# RV1103.net
KiCad netlist of a schematic drawn in Altium Designer
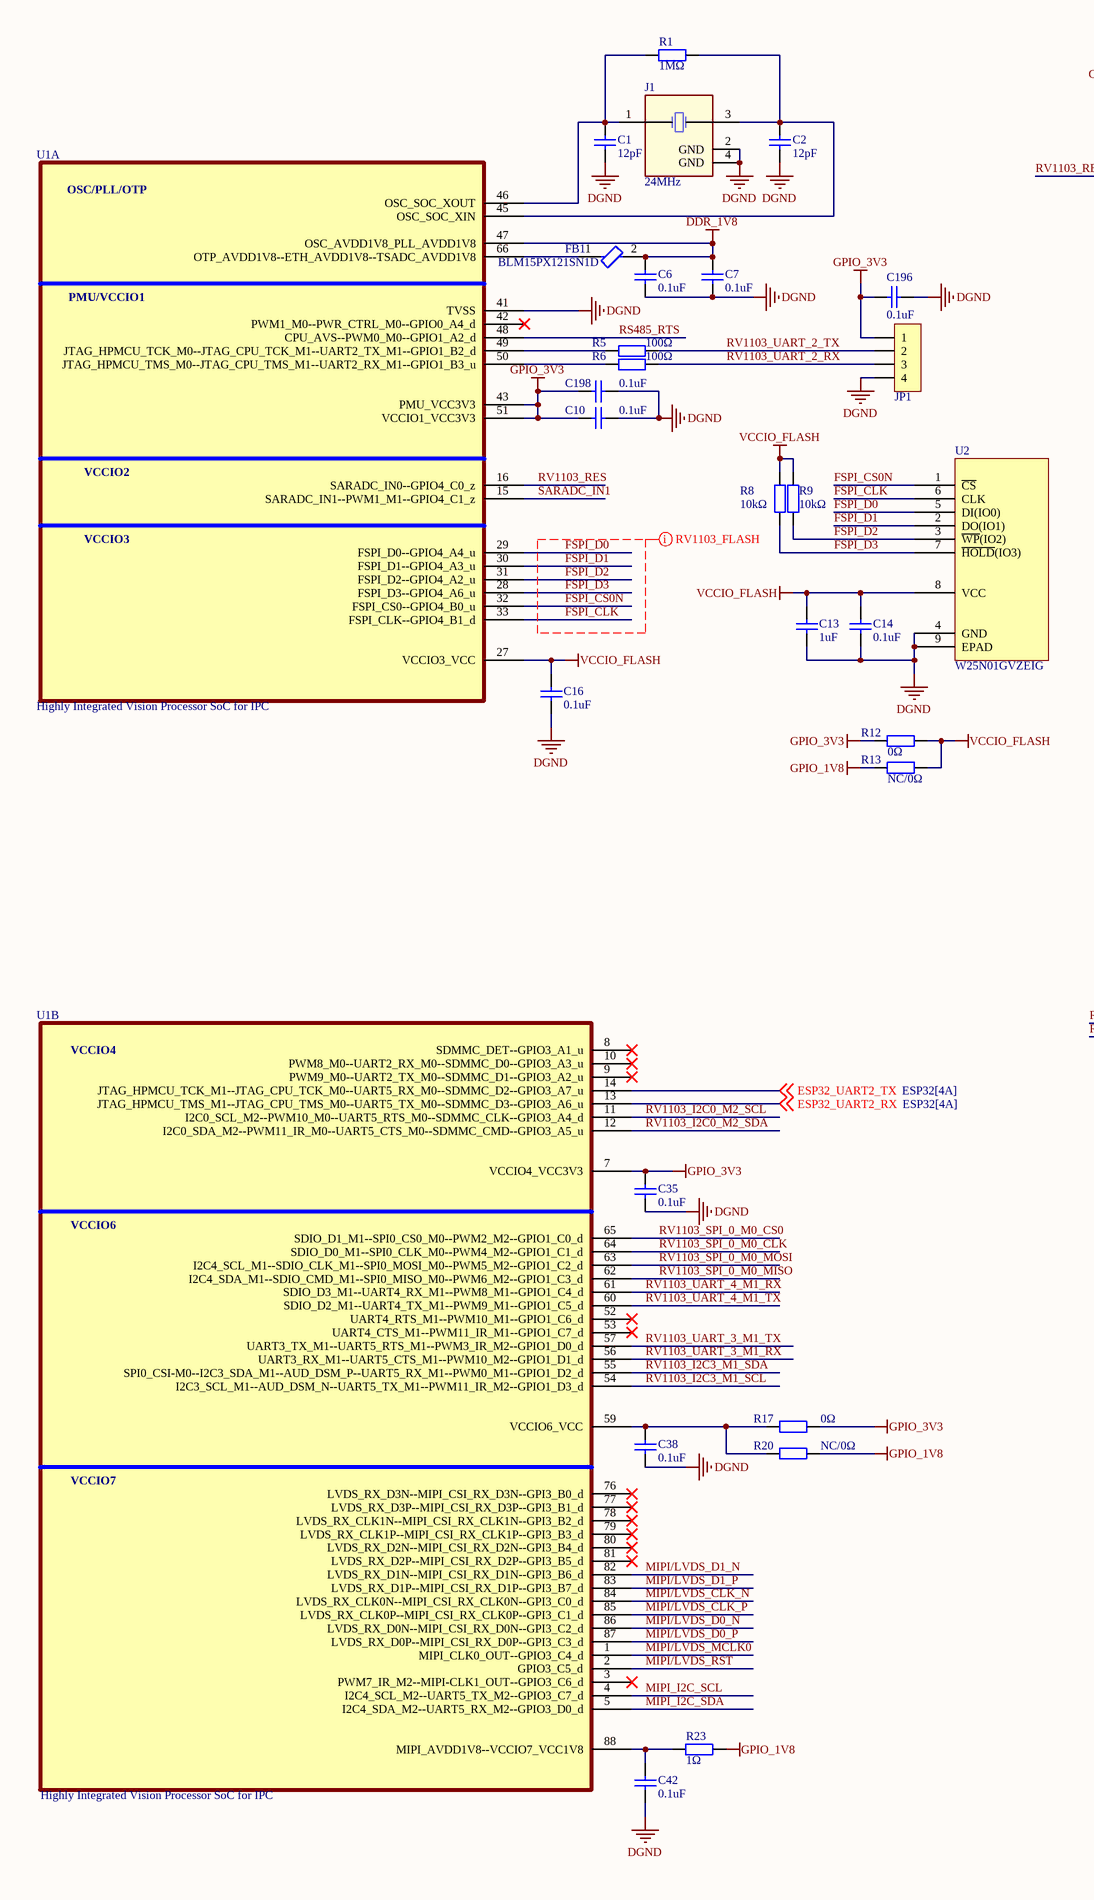
[diagram p0: RV1103.SchDoc, left]
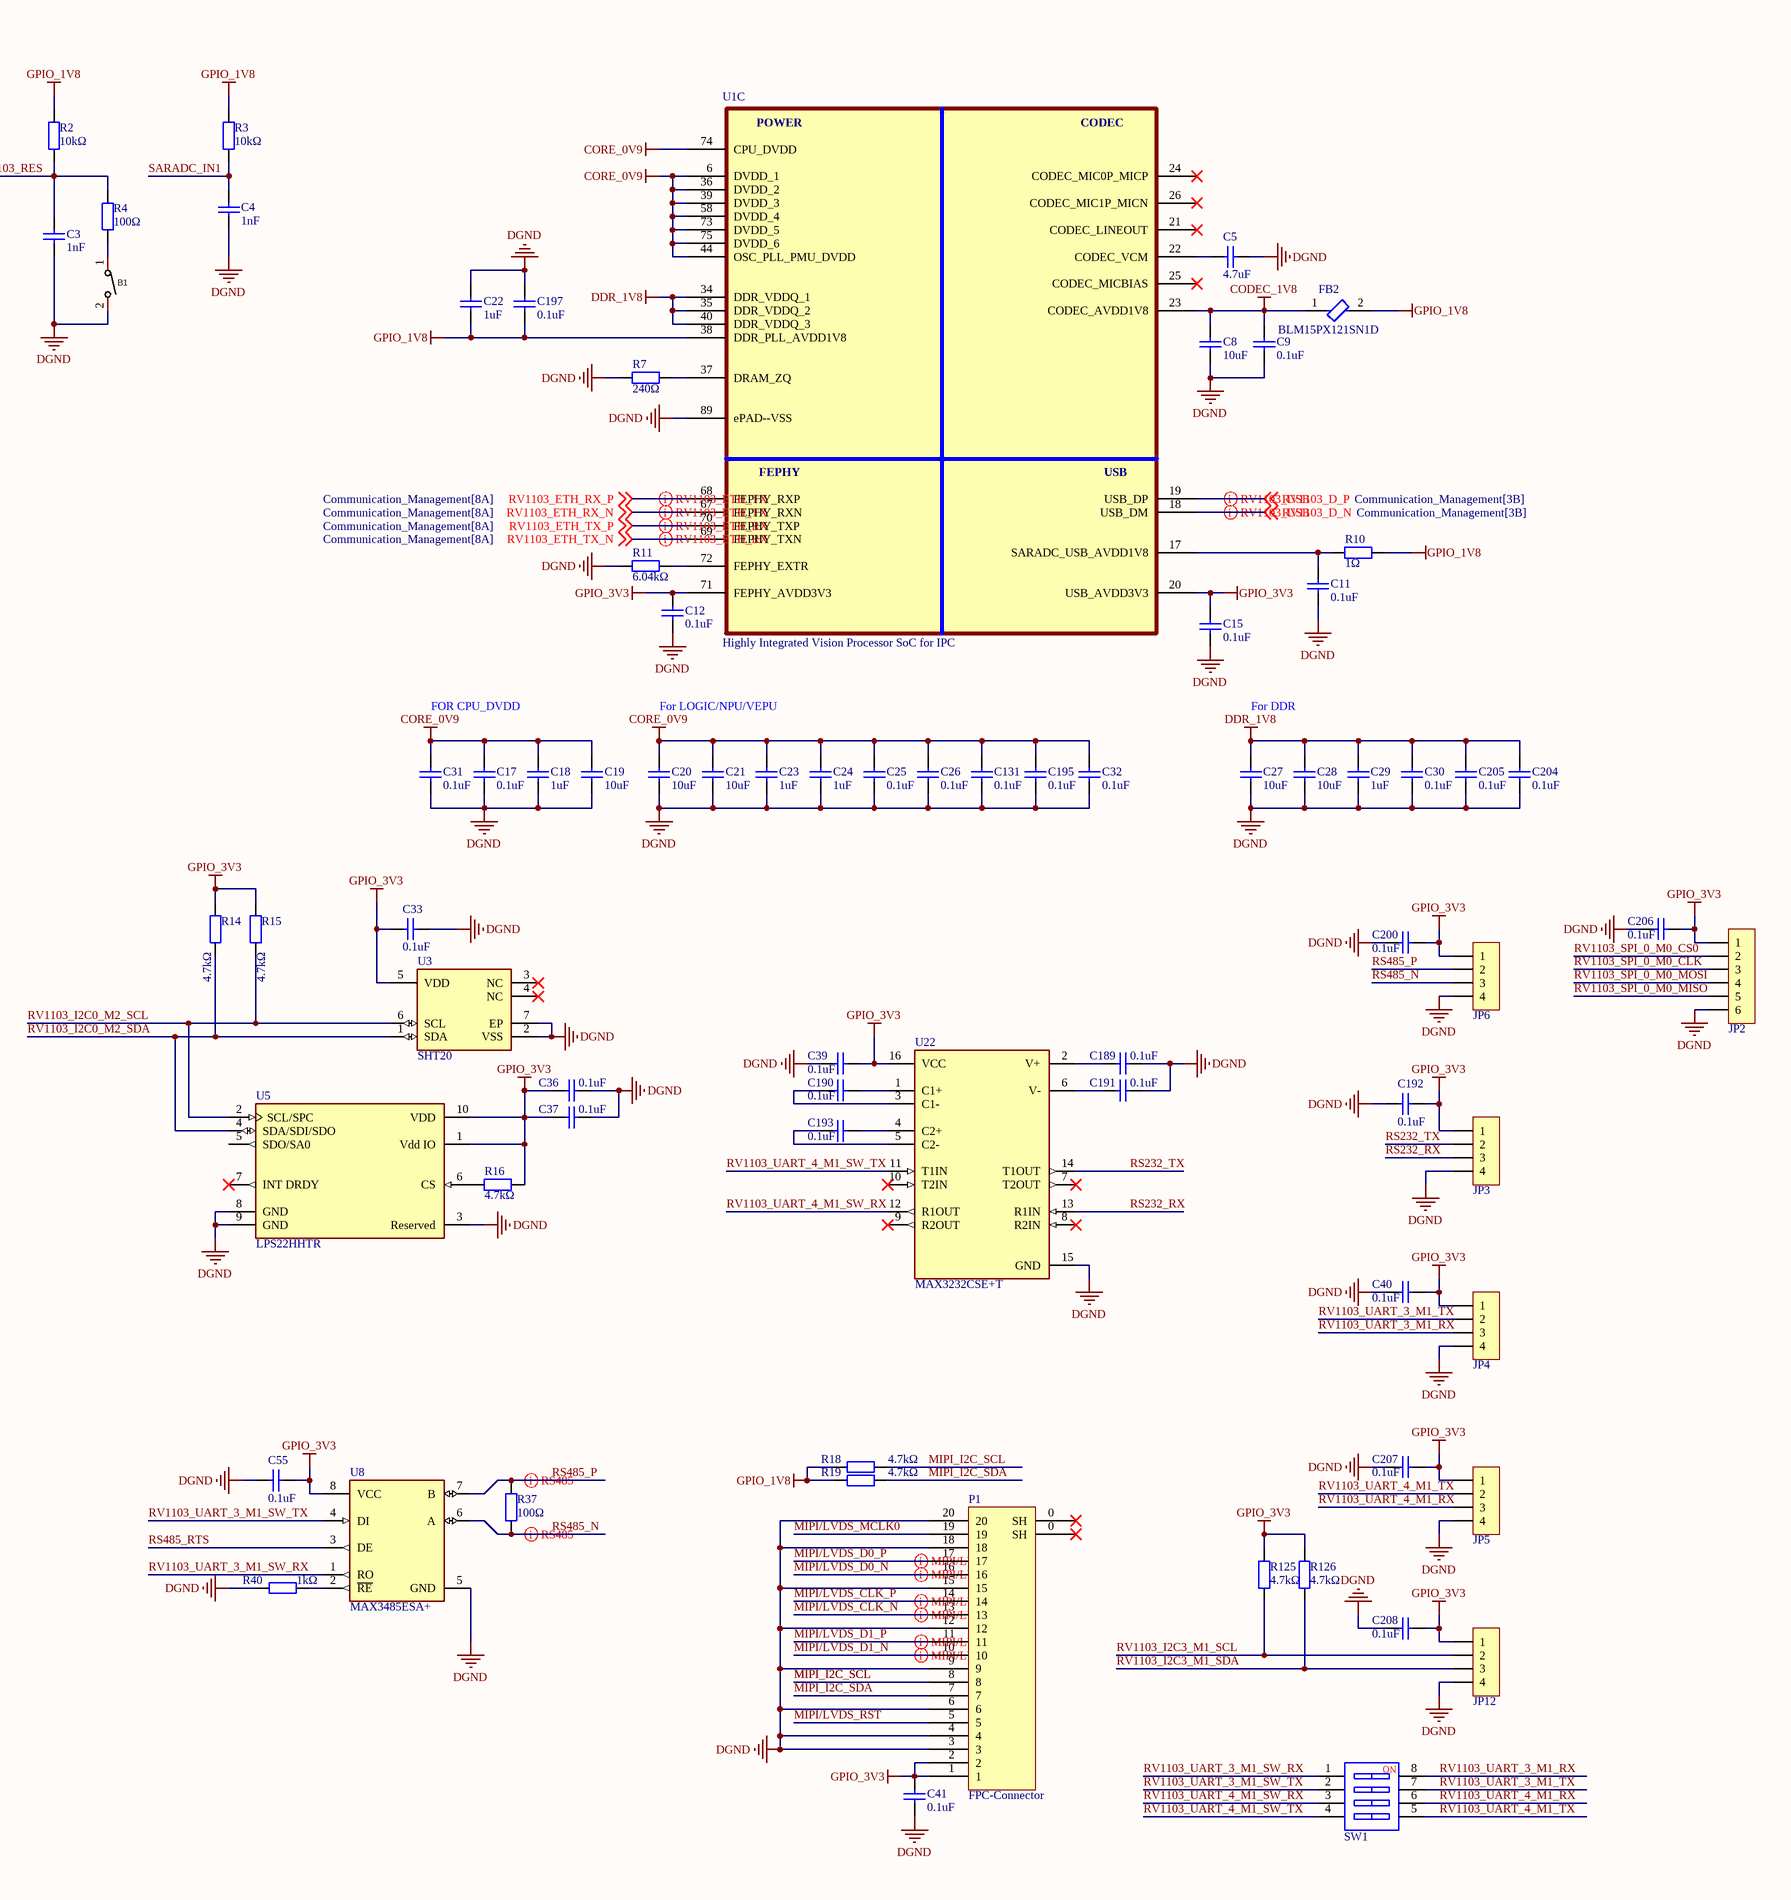
[diagram p1: RV1103.SchDoc, right]

(export (version "E")
  (design (tool "Eeschema 10.0.6"))
  (components
    (comp (ref "B1")
      (value "Bottom-2P-1Way")
      (footprint "SFerret:SW-SMD_L4.0-W2.9-LS5.0")
      (description "轻触按键")
      (fields (field (name "MANUFACTURER") "SHOU HAN(首韩)") (field (name "MANUFACTURER PART") "TS342A2P-WZ"))
      (libsource (lib "SFerret") (part "Bottom-2P-1Way"))
    )
    (comp (ref "C1")
      (value "12pF")
      (footprint "0402_C")
      (description "贴片电容")
      (libsource (lib "SFerret") (part "SMT_Cap"))
    )
    (comp (ref "C2")
      (value "12pF")
      (footprint "0402_C")
      (description "贴片电容")
      (libsource (lib "SFerret") (part "SMT_Cap"))
    )
    (comp (ref "C3")
      (value "1nF")
      (footprint "0402_C")
      (description "贴片电容")
      (libsource (lib "SFerret") (part "SMT_Cap"))
    )
    (comp (ref "C4")
      (value "1nF")
      (footprint "0402_C")
      (description "贴片电容")
      (libsource (lib "SFerret") (part "SMT_Cap"))
    )
    (comp (ref "C5")
      (value "4.7uF")
      (footprint "0402_C")
      (description "贴片电容")
      (libsource (lib "SFerret") (part "SMT_Cap"))
    )
    (comp (ref "C6")
      (value "0.1uF")
      (footprint "0402_C")
      (description "贴片电容")
      (libsource (lib "SFerret") (part "SMT_Cap"))
    )
    (comp (ref "C7")
      (value "0.1uF")
      (footprint "0402_C")
      (description "贴片电容")
      (libsource (lib "SFerret") (part "SMT_Cap"))
    )
    (comp (ref "C8")
      (value "10uF")
      (footprint "0402_C")
      (description "贴片电容")
      (libsource (lib "SFerret") (part "SMT_Cap"))
    )
    (comp (ref "C9")
      (value "0.1uF")
      (footprint "0402_C")
      (description "贴片电容")
      (libsource (lib "SFerret") (part "SMT_Cap"))
    )
    (comp (ref "C10")
      (value "0.1uF")
      (footprint "0402_C")
      (description "贴片电容")
      (libsource (lib "SFerret") (part "SMT_Cap"))
    )
    (comp (ref "C11")
      (value "0.1uF")
      (footprint "0402_C")
      (description "贴片电容")
      (libsource (lib "SFerret") (part "SMT_Cap"))
    )
    (comp (ref "C12")
      (value "0.1uF")
      (footprint "0402_C")
      (description "贴片电容")
      (libsource (lib "SFerret") (part "SMT_Cap"))
    )
    (comp (ref "C13")
      (value "1uF")
      (footprint "0603_C")
      (description "贴片电容")
      (libsource (lib "SFerret") (part "SMT_Cap"))
    )
    (comp (ref "C14")
      (value "0.1uF")
      (footprint "0603_C")
      (description "贴片电容")
      (libsource (lib "SFerret") (part "SMT_Cap"))
    )
    (comp (ref "C15")
      (value "0.1uF")
      (footprint "0402_C")
      (description "贴片电容")
      (libsource (lib "SFerret") (part "SMT_Cap"))
    )
    (comp (ref "C16")
      (value "0.1uF")
      (footprint "0402_C")
      (description "贴片电容")
      (libsource (lib "SFerret") (part "SMT_Cap"))
    )
    (comp (ref "C17")
      (value "0.1uF")
      (footprint "0402_C")
      (description "贴片电容")
      (libsource (lib "SFerret") (part "SMT_Cap"))
    )
    (comp (ref "C18")
      (value "1uF")
      (footprint "0402_C")
      (description "贴片电容")
      (libsource (lib "SFerret") (part "SMT_Cap"))
    )
    (comp (ref "C19")
      (value "10uF")
      (footprint "0603_C")
      (description "贴片电容")
      (libsource (lib "SFerret") (part "SMT_Cap"))
    )
    (comp (ref "C20")
      (value "10uF")
      (footprint "0603_C")
      (description "贴片电容")
      (libsource (lib "SFerret") (part "SMT_Cap"))
    )
    (comp (ref "C21")
      (value "10uF")
      (footprint "0603_C")
      (description "贴片电容")
      (libsource (lib "SFerret") (part "SMT_Cap"))
    )
    (comp (ref "C22")
      (value "1uF")
      (footprint "0402_C")
      (description "贴片电容")
      (libsource (lib "SFerret") (part "SMT_Cap"))
    )
    (comp (ref "C23")
      (value "1uF")
      (footprint "0402_C")
      (description "贴片电容")
      (libsource (lib "SFerret") (part "SMT_Cap"))
    )
    (comp (ref "C24")
      (value "1uF")
      (footprint "0402_C")
      (description "贴片电容")
      (libsource (lib "SFerret") (part "SMT_Cap"))
    )
    (comp (ref "C25")
      (value "0.1uF")
      (footprint "0402_C")
      (description "贴片电容")
      (libsource (lib "SFerret") (part "SMT_Cap"))
    )
    (comp (ref "C26")
      (value "0.1uF")
      (footprint "0402_C")
      (description "贴片电容")
      (libsource (lib "SFerret") (part "SMT_Cap"))
    )
    (comp (ref "C27")
      (value "10uF")
      (footprint "0603_C")
      (description "贴片电容")
      (libsource (lib "SFerret") (part "SMT_Cap"))
    )
    (comp (ref "C28")
      (value "10uF")
      (footprint "0603_C")
      (description "贴片电容")
      (libsource (lib "SFerret") (part "SMT_Cap"))
    )
    (comp (ref "C29")
      (value "1uF")
      (footprint "0402_C")
      (description "贴片电容")
      (libsource (lib "SFerret") (part "SMT_Cap"))
    )
    (comp (ref "C30")
      (value "0.1uF")
      (footprint "0402_C")
      (description "贴片电容")
      (libsource (lib "SFerret") (part "SMT_Cap"))
    )
    (comp (ref "C31")
      (value "0.1uF")
      (footprint "0402_C")
      (description "贴片电容")
      (libsource (lib "SFerret") (part "SMT_Cap"))
    )
    (comp (ref "C32")
      (value "0.1uF")
      (footprint "0402_C")
      (description "贴片电容")
      (libsource (lib "SFerret") (part "SMT_Cap"))
    )
    (comp (ref "C33")
      (value "0.1uF")
      (footprint "0603_C")
      (description "贴片电容")
      (libsource (lib "SFerret") (part "SMT_Cap"))
    )
    (comp (ref "C35")
      (value "0.1uF")
      (footprint "0402_C")
      (description "贴片电容")
      (libsource (lib "SFerret") (part "SMT_Cap"))
    )
    (comp (ref "C36")
      (value "0.1uF")
      (footprint "0603_C")
      (description "贴片电容")
      (libsource (lib "SFerret") (part "SMT_Cap"))
    )
    (comp (ref "C37")
      (value "0.1uF")
      (footprint "0603_C")
      (description "贴片电容")
      (libsource (lib "SFerret") (part "SMT_Cap"))
    )
    (comp (ref "C38")
      (value "0.1uF")
      (footprint "0402_C")
      (description "贴片电容")
      (libsource (lib "SFerret") (part "SMT_Cap"))
    )
    (comp (ref "C39")
      (value "0.1uF")
      (footprint "0603_C")
      (description "贴片电容")
      (libsource (lib "SFerret") (part "SMT_Cap"))
    )
    (comp (ref "C40")
      (value "0.1uF")
      (footprint "0603_C")
      (description "贴片电容")
      (libsource (lib "SFerret") (part "SMT_Cap"))
    )
    (comp (ref "C41")
      (value "0.1uF")
      (footprint "0603_C")
      (description "贴片电容")
      (libsource (lib "SFerret") (part "SMT_Cap"))
    )
    (comp (ref "C42")
      (value "0.1uF")
      (footprint "0402_C")
      (description "贴片电容")
      (libsource (lib "SFerret") (part "SMT_Cap"))
    )
    (comp (ref "C55")
      (value "0.1uF")
      (footprint "0603_C")
      (description "贴片电容")
      (libsource (lib "SFerret") (part "SMT_Cap"))
    )
    (comp (ref "C131")
      (value "0.1uF")
      (footprint "0402_C")
      (description "贴片电容")
      (libsource (lib "SFerret") (part "SMT_Cap"))
    )
    (comp (ref "C189")
      (value "0.1uF")
      (footprint "0603_C")
      (description "贴片电容")
      (libsource (lib "SFerret") (part "SMT_Cap"))
    )
    (comp (ref "C190")
      (value "0.1uF")
      (footprint "0603_C")
      (description "贴片电容")
      (libsource (lib "SFerret") (part "SMT_Cap"))
    )
    (comp (ref "C191")
      (value "0.1uF")
      (footprint "0603_C")
      (description "贴片电容")
      (libsource (lib "SFerret") (part "SMT_Cap"))
    )
    (comp (ref "C192")
      (value "0.1uF")
      (footprint "0603_C")
      (description "贴片电容")
      (libsource (lib "SFerret") (part "SMT_Cap"))
    )
    (comp (ref "C193")
      (value "0.1uF")
      (footprint "0603_C")
      (description "贴片电容")
      (libsource (lib "SFerret") (part "SMT_Cap"))
    )
    (comp (ref "C195")
      (value "0.1uF")
      (footprint "0402_C")
      (description "贴片电容")
      (libsource (lib "SFerret") (part "SMT_Cap"))
    )
    (comp (ref "C196")
      (value "0.1uF")
      (footprint "0603_C")
      (description "贴片电容")
      (libsource (lib "SFerret") (part "SMT_Cap"))
    )
    (comp (ref "C197")
      (value "0.1uF")
      (footprint "0402_C")
      (description "贴片电容")
      (libsource (lib "SFerret") (part "SMT_Cap"))
    )
    (comp (ref "C198")
      (value "0.1uF")
      (footprint "0402_C")
      (description "贴片电容")
      (libsource (lib "SFerret") (part "SMT_Cap"))
    )
    (comp (ref "C200")
      (value "0.1uF")
      (footprint "0603_C")
      (description "贴片电容")
      (libsource (lib "SFerret") (part "SMT_Cap"))
    )
    (comp (ref "C204")
      (value "0.1uF")
      (footprint "0402_C")
      (description "贴片电容")
      (libsource (lib "SFerret") (part "SMT_Cap"))
    )
    (comp (ref "C205")
      (value "0.1uF")
      (footprint "0402_C")
      (description "贴片电容")
      (libsource (lib "SFerret") (part "SMT_Cap"))
    )
    (comp (ref "C206")
      (value "0.1uF")
      (footprint "0603_C")
      (description "贴片电容")
      (libsource (lib "SFerret") (part "SMT_Cap"))
    )
    (comp (ref "C207")
      (value "0.1uF")
      (footprint "0603_C")
      (description "贴片电容")
      (libsource (lib "SFerret") (part "SMT_Cap"))
    )
    (comp (ref "C208")
      (value "0.1uF")
      (footprint "0603_C")
      (description "贴片电容")
      (libsource (lib "SFerret") (part "SMT_Cap"))
    )
    (comp (ref "FB1")
      (value "BLM15PX121SN1D")
      (footprint "FP-BLM15-0_05-d0_7-MFG")
      (description "Chip Ferrite Bead, 0402, 120Ω @ 100MHz, 0.055Ω, 25%, 2A")
      (fields (field (name "TOLERANCE") "25%"))
      (libsource (lib "Altium Content Vault") (part "5f30dd21d616792df468990f7003faa"))
    )
    (comp (ref "FB2")
      (value "BLM15PX121SN1D")
      (footprint "FP-BLM15-0_05-d0_7-MFG")
      (description "Chip Ferrite Bead, 0402, 120Ω @ 100MHz, 0.055Ω, 25%, 2A")
      (fields (field (name "TOLERANCE") "25%"))
      (libsource (lib "Altium Content Vault") (part "5f30dd21d616792df468990f7003faa"))
    )
    (comp (ref "J1")
      (value "24MHz")
      (footprint "SMD-2520_4P")
      (libsource (lib "SFerret") (part "Oscillator_SMT_4P"))
    )
    (comp (ref "JP1")
      (value "HDR-1X4")
      (footprint "MX 1.25-LS-4P")
      (description "4P接插件")
      (libsource (lib "5.0 - 接插件-脚距1.25") (part "Header 4"))
    )
    (comp (ref "JP2")
      (value "HDR-1X6")
      (footprint "MX 1.25-LS-6P")
      (description "6P接插件")
      (libsource (lib "5.0 - 接插件-脚距1.25") (part "Header 6"))
    )
    (comp (ref "JP3")
      (value "HDR-1X4")
      (footprint "MX 1.25-LS-4P")
      (description "4P接插件")
      (libsource (lib "5.0 - 接插件-脚距1.25") (part "Header 4"))
    )
    (comp (ref "JP4")
      (value "HDR-1X4")
      (footprint "MX 1.25-LS-4P")
      (description "4P接插件")
      (libsource (lib "5.0 - 接插件-脚距1.25") (part "Header 4"))
    )
    (comp (ref "JP5")
      (value "HDR-1X4")
      (footprint "MX 1.25-LS-4P")
      (description "4P接插件")
      (libsource (lib "5.0 - 接插件-脚距1.25") (part "Header 4"))
    )
    (comp (ref "JP6")
      (value "HDR-1X4")
      (footprint "MX 1.25-LS-4P")
      (description "4P接插件")
      (libsource (lib "5.0 - 接插件-脚距1.25") (part "Header 4"))
    )
    (comp (ref "JP12")
      (value "HDR-1X4")
      (footprint "MX 1.25-LS-4P")
      (description "4P接插件")
      (libsource (lib "5.0 - 接插件-脚距1.25") (part "Header 4"))
    )
    (comp (ref "P1")
      (value "FPC-Connector")
      (footprint "FPC0.5 2H-WS-20P")
      (libsource (lib "SFerret") (part "FFC/FPC-0.5-WS-20"))
    )
    (comp (ref "R1")
      (value "1MΩ")
      (footprint "0402_R")
      (description "贴片电阻")
      (libsource (lib "") (part "SMT_Res_1"))
    )
    (comp (ref "R2")
      (value "10kΩ")
      (footprint "0402_R")
      (description "贴片电阻")
      (libsource (lib "SFerret") (part "SMT_Res"))
    )
    (comp (ref "R3")
      (value "10kΩ")
      (footprint "0402_R")
      (description "贴片电阻")
      (libsource (lib "SFerret") (part "SMT_Res"))
    )
    (comp (ref "R4")
      (value "100Ω")
      (footprint "0402_R")
      (description "贴片电阻")
      (libsource (lib "SFerret") (part "SMT_Res"))
    )
    (comp (ref "R5")
      (value "100Ω")
      (footprint "0402_R")
      (description "贴片电阻")
      (libsource (lib "") (part "SMT_Res_1"))
    )
    (comp (ref "R6")
      (value "100Ω")
      (footprint "0402_R")
      (description "贴片电阻")
      (libsource (lib "") (part "SMT_Res_1"))
    )
    (comp (ref "R7")
      (value "240Ω")
      (footprint "0402_R")
      (description "贴片电阻")
      (libsource (lib "") (part "SMT_Res_1"))
    )
    (comp (ref "R8")
      (value "10kΩ")
      (footprint "0603_R")
      (description "贴片电阻")
      (libsource (lib "SFerret") (part "SMT_Res"))
    )
    (comp (ref "R9")
      (value "10kΩ")
      (footprint "0603_R")
      (description "贴片电阻")
      (libsource (lib "SFerret") (part "SMT_Res"))
    )
    (comp (ref "R10")
      (value "1Ω")
      (footprint "0402_R")
      (description "贴片电阻")
      (libsource (lib "") (part "SMT_Res_1"))
    )
    (comp (ref "R11")
      (value "6.04kΩ")
      (footprint "0402_R")
      (description "贴片电阻")
      (libsource (lib "") (part "SMT_Res_1"))
    )
    (comp (ref "R12")
      (value "0Ω")
      (footprint "0402_R")
      (description "贴片电阻")
      (libsource (lib "") (part "SMT_Res_1"))
    )
    (comp (ref "R13")
      (value "NC/0Ω")
      (footprint "0402_R")
      (description "贴片电阻")
      (libsource (lib "") (part "SMT_Res_1"))
    )
    (comp (ref "R14")
      (value "4.7kΩ")
      (footprint "0603_R")
      (description "贴片电阻")
      (libsource (lib "SFerret") (part "SMT_Res"))
    )
    (comp (ref "R15")
      (value "4.7kΩ")
      (footprint "0603_R")
      (description "贴片电阻")
      (libsource (lib "SFerret") (part "SMT_Res"))
    )
    (comp (ref "R16")
      (value "4.7kΩ")
      (footprint "0603_R")
      (description "贴片电阻")
      (libsource (lib "") (part "SMT_Res_2"))
    )
    (comp (ref "R17")
      (value "0Ω")
      (footprint "0402_R")
      (description "贴片电阻")
      (libsource (lib "") (part "SMT_Res_1"))
    )
    (comp (ref "R18")
      (value "4.7kΩ")
      (footprint "0402_R")
      (description "贴片电阻")
      (libsource (lib "") (part "SMT_Res_2"))
    )
    (comp (ref "R19")
      (value "4.7kΩ")
      (footprint "0402_R")
      (description "贴片电阻")
      (libsource (lib "") (part "SMT_Res_2"))
    )
    (comp (ref "R20")
      (value "NC/0Ω")
      (footprint "0402_R")
      (description "贴片电阻")
      (libsource (lib "") (part "SMT_Res_1"))
    )
    (comp (ref "R23")
      (value "1Ω")
      (footprint "0402_R")
      (description "贴片电阻")
      (libsource (lib "") (part "SMT_Res_1"))
    )
    (comp (ref "R37")
      (value "100Ω")
      (footprint "0805_R")
      (description "贴片电阻")
      (libsource (lib "SFerret") (part "SMT_Res"))
    )
    (comp (ref "R40")
      (value "1kΩ")
      (footprint "0603_R")
      (description "贴片电阻")
      (libsource (lib "") (part "SMT_Res_2"))
    )
    (comp (ref "R125")
      (value "4.7kΩ")
      (footprint "0402_R")
      (description "贴片电阻")
      (libsource (lib "SFerret") (part "SMT_Res"))
    )
    (comp (ref "R126")
      (value "4.7kΩ")
      (footprint "0402_R")
      (description "贴片电阻")
      (libsource (lib "SFerret") (part "SMT_Res"))
    )
    (comp (ref "SW1")
      (value "SW-4P")
      (footprint "CSW1.27 SMD-4P")
      (description "4路编码开关")
      (libsource (lib "0.7 - 常用按键-开关-蜂鸣器-电池") (part "SW-4P"))
    )
    (comp (ref "U1")
      (value "Highly Integrated Vision Processor SoC for IPC")
      (footprint "QFN35P900X900X95_HS-89N")
      (libsource (lib "SFerret") (part "RV1103G"))
    )
    (comp (ref "U2")
      (value "W25N01GVZEIG")
      (footprint "WSON-8_8X6_WIN")
      (description "1G-BIT SPI FLASH")
      (libsource (lib "SFerret") (part "W25N01GVZEIG"))
    )
    (comp (ref "U3")
      (value "SHT20")
      (footprint "FP-SHT20-MFG")
      (description "SENSOR HUMID/TEMP 3V I2C 3% SMD")
      (fields
        (field (name "OCTOPART") "https://octopart.com/sht20-sensirion-47077745")
        (field (name "MANUFACTURER") "Sensirion")
      )
      (libsource (lib "Altium Content Vault") (part "5058aba635ec8ccb61858bacc329a36"))
    )
    (comp (ref "U5")
      (value "LPS22HHTR")
      (footprint "FP-HLGA-10L-DM00386636-MFG")
      (description "CONSUMER MEMS")
      (fields
        (field (name "OCTOPART") "https://octopart.com/lps22hhtr-stmicroelectronics-94834025")
        (field (name "MANUFACTURER") "STMicroelectronics")
      )
      (libsource (lib "Altium Content Vault") (part "af158f922cca5ffd55045a3797efeaf"))
    )
    (comp (ref "U8")
      (value "MAX3485ESA+")
      (footprint "FP-S8-5-MFG")
      (description "IC TXRX RS485/422 10MBPS 8SOIC")
      (fields
        (field (name "OCTOPART") "https://octopart.com/max3485esa%2B-maxim+integrated-39731860")
        (field (name "MANUFACTURER") "Maxim Integrated")
      )
      (libsource (lib "Altium Content Vault") (part "336746e10bf8cc649a8da99b4f6b1f2"))
    )
    (comp (ref "U22")
      (value "MAX3232CSE+T")
      (footprint "FP-S16-1-MFG")
      (description "IC TXRX RS-232 LP 16SOIC")
      (fields
        (field (name "OCTOPART") "https://octopart.com/max3232cse%2Bt-maxim+integrated-39731899")
        (field (name "MANUFACTURER") "Maxim Integrated")
      )
      (libsource (lib "Altium Content Vault") (part "80da13fa3a6e07794a93113addc51a4"))
    )
  )
  (nets
    (net (code "1") (name "/FSPI_CLK") (class "Default")
      (node (ref "U1") (pin "33") (pinfunction "FSPI_CLK--GPIO4_B1_d_33") (pintype "passive"))
      (node (ref "U2") (pin "6") (pinfunction "CLK_6") (pintype "passive"))
    )
    (net (code "2") (name "/FSPI_CS0N") (class "Default")
      (node (ref "U1") (pin "32") (pinfunction "FSPI_CS0--GPIO4_B0_u_32") (pintype "passive"))
      (node (ref "U2") (pin "1") (pinfunction "~{CS}_1") (pintype "passive"))
    )
    (net (code "3") (name "/FSPI_D0") (class "Default")
      (node (ref "U1") (pin "29") (pinfunction "FSPI_D0--GPIO4_A4_u_29") (pintype "passive"))
      (node (ref "U2") (pin "5") (pinfunction "DI(IO0)_5") (pintype "passive"))
    )
    (net (code "4") (name "/FSPI_D1") (class "Default")
      (node (ref "U1") (pin "30") (pinfunction "FSPI_D1--GPIO4_A3_u_30") (pintype "passive"))
      (node (ref "U2") (pin "2") (pinfunction "DO(IO1)_2") (pintype "passive"))
    )
    (net (code "5") (name "/FSPI_D2") (class "Default")
      (node (ref "R9") (pin "1") (pinfunction "1_1") (pintype "passive"))
      (node (ref "U1") (pin "31") (pinfunction "FSPI_D2--GPIO4_A2_u_31") (pintype "passive"))
      (node (ref "U2") (pin "3") (pinfunction "~{WP}(IO2)_3") (pintype "passive"))
    )
    (net (code "6") (name "/FSPI_D3") (class "Default")
      (node (ref "R8") (pin "1") (pinfunction "1_1") (pintype "passive"))
      (node (ref "U1") (pin "28") (pinfunction "FSPI_D3--GPIO4_A6_u_28") (pintype "passive"))
      (node (ref "U2") (pin "7") (pinfunction "~{HOLD}(IO3)_7") (pintype "passive"))
    )
    (net (code "7") (name "/MIPI_I2C_SCL") (class "Default")
      (node (ref "P1") (pin "8") (pinfunction "8_8") (pintype "passive"))
      (node (ref "R18") (pin "1") (pinfunction "1_1") (pintype "passive"))
      (node (ref "U1") (pin "4") (pinfunction "I2C4_SCL_M2--UART5_TX_M2--GPIO3_C7_d_4") (pintype "passive"))
    )
    (net (code "8") (name "/MIPI_I2C_SDA") (class "Default")
      (node (ref "P1") (pin "7") (pinfunction "7_7") (pintype "passive"))
      (node (ref "R19") (pin "1") (pinfunction "1_1") (pintype "passive"))
      (node (ref "U1") (pin "5") (pinfunction "I2C4_SDA_M2--UART5_RX_M2--GPIO3_D0_d_5") (pintype "passive"))
    )
    (net (code "9") (name "/MIPI{slash}LVDS_CLK_N") (class "Default")
      (node (ref "P1") (pin "13") (pinfunction "13_13") (pintype "passive"))
      (node (ref "U1") (pin "84") (pinfunction "LVDS_RX_CLK0N--MIPI_CSI_RX_CLK0N--GPI3_C0_d_84") (pintype "passive"))
    )
    (net (code "10") (name "/MIPI{slash}LVDS_CLK_P") (class "Default")
      (node (ref "P1") (pin "14") (pinfunction "14_14") (pintype "passive"))
      (node (ref "U1") (pin "85") (pinfunction "LVDS_RX_CLK0P--MIPI_CSI_RX_CLK0P--GPI3_C1_d_85") (pintype "passive"))
    )
    (net (code "11") (name "/MIPI{slash}LVDS_D0_N") (class "Default")
      (node (ref "P1") (pin "16") (pinfunction "16_16") (pintype "passive"))
      (node (ref "U1") (pin "86") (pinfunction "LVDS_RX_D0N--MIPI_CSI_RX_D0N--GPI3_C2_d_86") (pintype "passive"))
    )
    (net (code "12") (name "/MIPI{slash}LVDS_D0_P") (class "Default")
      (node (ref "P1") (pin "17") (pinfunction "17_17") (pintype "passive"))
      (node (ref "U1") (pin "87") (pinfunction "LVDS_RX_D0P--MIPI_CSI_RX_D0P--GPI3_C3_d_87") (pintype "passive"))
    )
    (net (code "13") (name "/MIPI{slash}LVDS_D1_N") (class "Default")
      (node (ref "P1") (pin "10") (pinfunction "10_10") (pintype "passive"))
      (node (ref "U1") (pin "82") (pinfunction "LVDS_RX_D1N--MIPI_CSI_RX_D1N--GPI3_B6_d_82") (pintype "passive"))
    )
    (net (code "14") (name "/MIPI{slash}LVDS_D1_P") (class "Default")
      (node (ref "P1") (pin "11") (pinfunction "11_11") (pintype "passive"))
      (node (ref "U1") (pin "83") (pinfunction "LVDS_RX_D1P--MIPI_CSI_RX_D1P--GPI3_B7_d_83") (pintype "passive"))
    )
    (net (code "15") (name "/MIPI{slash}LVDS_MCLK0") (class "Default")
      (node (ref "P1") (pin "19") (pinfunction "19_19") (pintype "passive"))
      (node (ref "U1") (pin "1") (pinfunction "MIPI_CLK0_OUT--GPIO3_C4_d_1") (pintype "passive"))
    )
    (net (code "16") (name "/MIPI{slash}LVDS_RST") (class "Default")
      (node (ref "P1") (pin "5") (pinfunction "5_5") (pintype "passive"))
      (node (ref "U1") (pin "2") (pinfunction "GPIO3_C5_d_2") (pintype "passive"))
    )
    (net (code "17") (name "/RS232_RX") (class "Default")
      (node (ref "JP3") (pin "3") (pinfunction "3_3") (pintype "passive"))
      (node (ref "U22") (pin "13") (pinfunction "R1IN_13") (pintype "input"))
    )
    (net (code "18") (name "/RS232_TX") (class "Default")
      (node (ref "JP3") (pin "2") (pinfunction "2_2") (pintype "passive"))
      (node (ref "U22") (pin "14") (pinfunction "T1OUT_14") (pintype "output"))
    )
    (net (code "19") (name "/RS485_N") (class "Default")
      (node (ref "JP6") (pin "3") (pinfunction "3_3") (pintype "passive"))
      (node (ref "R37") (pin "1") (pinfunction "1_1") (pintype "passive"))
      (node (ref "U8") (pin "6") (pinfunction "A_6") (pintype "bidirectional"))
    )
    (net (code "20") (name "/RS485_P") (class "Default")
      (node (ref "JP6") (pin "2") (pinfunction "2_2") (pintype "passive"))
      (node (ref "R37") (pin "2") (pinfunction "2_2") (pintype "passive"))
      (node (ref "U8") (pin "7") (pinfunction "B_7") (pintype "bidirectional"))
    )
    (net (code "21") (name "/RS485_RTS") (class "Default")
      (node (ref "U1") (pin "48") (pinfunction "CPU_AVS--PWM0_M0--GPIO1_A2_d_48") (pintype "passive"))
      (node (ref "U8") (pin "3") (pinfunction "DE_3") (pintype "output"))
    )
    (net (code "22") (name "/RV1103_I2C0_M2_SCL") (class "Default")
      (node (ref "R15") (pin "1") (pinfunction "1_1") (pintype "passive"))
      (node (ref "U1") (pin "11") (pinfunction "I2C0_SCL_M2--PWM10_M0--UART5_RTS_M0--SDMMC_CLK--GPIO3_A4_d_11") (pintype "passive"))
      (node (ref "U3") (pin "6") (pinfunction "SCL_6") (pintype "bidirectional"))
      (node (ref "U5") (pin "2") (pinfunction "SCL/SPC_2") (pintype "input"))
    )
    (net (code "23") (name "/RV1103_I2C0_M2_SDA") (class "Default")
      (node (ref "R14") (pin "1") (pinfunction "1_1") (pintype "passive"))
      (node (ref "U1") (pin "12") (pinfunction "I2C0_SDA_M2--PWM11_IR_M0--UART5_CTS_M0--SDMMC_CMD--GPIO3_A5_u_12") (pintype "passive"))
      (node (ref "U3") (pin "1") (pinfunction "SDA_1") (pintype "bidirectional"))
      (node (ref "U5") (pin "4") (pinfunction "SDA/SDI/SDO_4") (pintype "bidirectional"))
    )
    (net (code "24") (name "/RV1103_I2C3_M1_SCL") (class "Default")
      (node (ref "JP12") (pin "2") (pinfunction "2_2") (pintype "passive"))
      (node (ref "R125") (pin "1") (pinfunction "1_1") (pintype "passive"))
      (node (ref "U1") (pin "54") (pinfunction "I2C3_SCL_M1--AUD_DSM_N--UART5_TX_M1--PWM11_IR_M2--GPIO1_D3_d_54") (pintype "passive"))
    )
    (net (code "25") (name "/RV1103_I2C3_M1_SDA") (class "Default")
      (node (ref "JP12") (pin "3") (pinfunction "3_3") (pintype "passive"))
      (node (ref "R126") (pin "1") (pinfunction "1_1") (pintype "passive"))
      (node (ref "U1") (pin "55") (pinfunction "SPI0_CSI-M0--I2C3_SDA_M1--AUD_DSM_P--UART5_RX_M1--PWM0_M1--GPIO1_D2_d_55") (pintype "passive"))
    )
    (net (code "26") (name "/RV1103_RES") (class "Default")
      (node (ref "C3") (pin "2") (pinfunction "2_2") (pintype "passive"))
      (node (ref "R2") (pin "1") (pinfunction "1_1") (pintype "passive"))
      (node (ref "R4") (pin "2") (pinfunction "2_2") (pintype "passive"))
      (node (ref "U1") (pin "16") (pinfunction "SARADC_IN0--GPIO4_C0_z_16") (pintype "passive"))
    )
    (net (code "27") (name "/RV1103_SPI_0_M0_CLK") (class "Default")
      (node (ref "JP2") (pin "3") (pinfunction "3_3") (pintype "passive"))
      (node (ref "U1") (pin "64") (pinfunction "SDIO_D0_M1--SPI0_CLK_M0--PWM4_M2--GPIO1_C1_d_64") (pintype "passive"))
    )
    (net (code "28") (name "/RV1103_SPI_0_M0_CS0") (class "Default")
      (node (ref "JP2") (pin "2") (pinfunction "2_2") (pintype "passive"))
      (node (ref "U1") (pin "65") (pinfunction "SDIO_D1_M1--SPI0_CS0_M0--PWM2_M2--GPIO1_C0_d_65") (pintype "passive"))
    )
    (net (code "29") (name "/RV1103_SPI_0_M0_MISO") (class "Default")
      (node (ref "JP2") (pin "5") (pinfunction "5_5") (pintype "passive"))
      (node (ref "U1") (pin "62") (pinfunction "I2C4_SDA_M1--SDIO_CMD_M1--SPI0_MISO_M0--PWM6_M2--GPIO1_C3_d_62") (pintype "passive"))
    )
    (net (code "30") (name "/RV1103_SPI_0_M0_MOSI") (class "Default")
      (node (ref "JP2") (pin "4") (pinfunction "4_4") (pintype "passive"))
      (node (ref "U1") (pin "63") (pinfunction "I2C4_SCL_M1--SDIO_CLK_M1--SPI0_MOSI_M0--PWM5_M2--GPIO1_C2_d_63") (pintype "passive"))
    )
    (net (code "31") (name "/RV1103_UART_2_RX") (class "Default")
      (node (ref "JP1") (pin "3") (pinfunction "3_3") (pintype "passive"))
      (node (ref "R6") (pin "2") (pinfunction "2_2") (pintype "passive"))
    )
    (net (code "32") (name "/RV1103_UART_2_TX") (class "Default")
      (node (ref "JP1") (pin "2") (pinfunction "2_2") (pintype "passive"))
      (node (ref "R5") (pin "2") (pinfunction "2_2") (pintype "passive"))
    )
    (net (code "33") (name "/RV1103_UART_3_M1_RX") (class "Default")
      (node (ref "JP4") (pin "3") (pinfunction "3_3") (pintype "passive"))
      (node (ref "SW1") (pin "8") (pinfunction "8_8") (pintype "passive"))
      (node (ref "U1") (pin "56") (pinfunction "UART3_RX_M1--UART5_CTS_M1--PWM10_M2--GPIO1_D1_d_56") (pintype "passive"))
    )
    (net (code "34") (name "/RV1103_UART_3_M1_SW_RX") (class "Default")
      (node (ref "SW1") (pin "1") (pinfunction "1_1") (pintype "passive"))
      (node (ref "U8") (pin "1") (pinfunction "RO_1") (pintype "output"))
    )
    (net (code "35") (name "/RV1103_UART_3_M1_SW_TX") (class "Default")
      (node (ref "SW1") (pin "2") (pinfunction "2_2") (pintype "passive"))
      (node (ref "U8") (pin "4") (pinfunction "DI_4") (pintype "input"))
    )
    (net (code "36") (name "/RV1103_UART_3_M1_TX") (class "Default")
      (node (ref "JP4") (pin "2") (pinfunction "2_2") (pintype "passive"))
      (node (ref "SW1") (pin "7") (pinfunction "7_7") (pintype "passive"))
      (node (ref "U1") (pin "57") (pinfunction "UART3_TX_M1--UART5_RTS_M1--PWM3_IR_M2--GPIO1_D0_d_57") (pintype "passive"))
    )
    (net (code "37") (name "/RV1103_UART_4_M1_RX") (class "Default")
      (node (ref "JP5") (pin "3") (pinfunction "3_3") (pintype "passive"))
      (node (ref "SW1") (pin "6") (pinfunction "6_6") (pintype "passive"))
      (node (ref "U1") (pin "61") (pinfunction "SDIO_D3_M1--UART4_RX_M1--PWM8_M1--GPIO1_C4_d_61") (pintype "passive"))
    )
    (net (code "38") (name "/RV1103_UART_4_M1_SW_RX") (class "Default")
      (node (ref "SW1") (pin "3") (pinfunction "3_3") (pintype "passive"))
      (node (ref "U22") (pin "12") (pinfunction "R1OUT_12") (pintype "output"))
    )
    (net (code "39") (name "/RV1103_UART_4_M1_SW_TX") (class "Default")
      (node (ref "SW1") (pin "4") (pinfunction "4_4") (pintype "passive"))
      (node (ref "U22") (pin "11") (pinfunction "T1IN_11") (pintype "input"))
    )
    (net (code "40") (name "/RV1103_UART_4_M1_TX") (class "Default")
      (node (ref "JP5") (pin "2") (pinfunction "2_2") (pintype "passive"))
      (node (ref "SW1") (pin "5") (pinfunction "5_5") (pintype "passive"))
      (node (ref "U1") (pin "60") (pinfunction "SDIO_D2_M1--UART4_TX_M1--PWM9_M1--GPIO1_C5_d_60") (pintype "passive"))
    )
    (net (code "41") (name "/SARADC_IN1") (class "Default")
      (node (ref "C4") (pin "2") (pinfunction "2_2") (pintype "passive"))
      (node (ref "R3") (pin "1") (pinfunction "1_1") (pintype "passive"))
      (node (ref "U1") (pin "15") (pinfunction "SARADC_IN1--PWM1_M1--GPIO4_C1_z_15") (pintype "passive"))
    )
    (net (code "42") (name "CODEC_1V8") (class "Default")
      (node (ref "C8") (pin "2") (pinfunction "2_2") (pintype "passive"))
      (node (ref "C9") (pin "2") (pinfunction "2_2") (pintype "passive"))
      (node (ref "FB2") (pin "1") (pinfunction "1_1") (pintype "passive"))
      (node (ref "U1") (pin "23") (pinfunction "CODEC_AVDD1V8_23") (pintype "passive"))
    )
    (net (code "43") (name "CORE_0V9") (class "Default")
      (node (ref "C131") (pin "2") (pinfunction "2_2") (pintype "passive"))
      (node (ref "C17") (pin "2") (pinfunction "2_2") (pintype "passive"))
      (node (ref "C18") (pin "2") (pinfunction "2_2") (pintype "passive"))
      (node (ref "C19") (pin "2") (pinfunction "2_2") (pintype "passive"))
      (node (ref "C195") (pin "2") (pinfunction "2_2") (pintype "passive"))
      (node (ref "C20") (pin "2") (pinfunction "2_2") (pintype "passive"))
      (node (ref "C21") (pin "2") (pinfunction "2_2") (pintype "passive"))
      (node (ref "C23") (pin "2") (pinfunction "2_2") (pintype "passive"))
      (node (ref "C24") (pin "2") (pinfunction "2_2") (pintype "passive"))
      (node (ref "C25") (pin "2") (pinfunction "2_2") (pintype "passive"))
      (node (ref "C26") (pin "2") (pinfunction "2_2") (pintype "passive"))
      (node (ref "C31") (pin "2") (pinfunction "2_2") (pintype "passive"))
      (node (ref "C32") (pin "2") (pinfunction "2_2") (pintype "passive"))
      (node (ref "U1") (pin "36") (pinfunction "DVDD_2_36") (pintype "passive"))
      (node (ref "U1") (pin "39") (pinfunction "DVDD_3_39") (pintype "passive"))
      (node (ref "U1") (pin "44") (pinfunction "OSC_PLL_PMU_DVDD_44") (pintype "passive"))
      (node (ref "U1") (pin "58") (pinfunction "DVDD_4_58") (pintype "passive"))
      (node (ref "U1") (pin "6") (pinfunction "DVDD_1_6") (pintype "passive"))
      (node (ref "U1") (pin "73") (pinfunction "DVDD_5_73") (pintype "passive"))
      (node (ref "U1") (pin "74") (pinfunction "CPU_DVDD_74") (pintype "passive"))
      (node (ref "U1") (pin "75") (pinfunction "DVDD_6_75") (pintype "passive"))
    )
    (net (code "44") (name "DDR_1V8") (class "Default")
      (node (ref "C204") (pin "2") (pinfunction "2_2") (pintype "passive"))
      (node (ref "C205") (pin "2") (pinfunction "2_2") (pintype "passive"))
      (node (ref "C27") (pin "2") (pinfunction "2_2") (pintype "passive"))
      (node (ref "C28") (pin "2") (pinfunction "2_2") (pintype "passive"))
      (node (ref "C29") (pin "2") (pinfunction "2_2") (pintype "passive"))
      (node (ref "C30") (pin "2") (pinfunction "2_2") (pintype "passive"))
      (node (ref "C6") (pin "1") (pinfunction "1_1") (pintype "passive"))
      (node (ref "C7") (pin "1") (pinfunction "1_1") (pintype "passive"))
      (node (ref "FB1") (pin "2") (pinfunction "2_2") (pintype "passive"))
      (node (ref "U1") (pin "34") (pinfunction "DDR_VDDQ_1_34") (pintype "passive"))
      (node (ref "U1") (pin "35") (pinfunction "DDR_VDDQ_2_35") (pintype "passive"))
      (node (ref "U1") (pin "40") (pinfunction "DDR_VDDQ_3_40") (pintype "passive"))
      (node (ref "U1") (pin "47") (pinfunction "OSC_AVDD1V8_PLL_AVDD1V8_47") (pintype "passive"))
    )
    (net (code "45") (name "DGND") (class "Default")
      (node (ref "B1") (pin "2") (pinfunction "2_2") (pintype "passive"))
      (node (ref "C1") (pin "1") (pinfunction "1_1") (pintype "passive"))
      (node (ref "C10") (pin "1") (pinfunction "1_1") (pintype "passive"))
      (node (ref "C11") (pin "1") (pinfunction "1_1") (pintype "passive"))
      (node (ref "C12") (pin "1") (pinfunction "1_1") (pintype "passive"))
      (node (ref "C13") (pin "1") (pinfunction "1_1") (pintype "passive"))
      (node (ref "C131") (pin "1") (pinfunction "1_1") (pintype "passive"))
      (node (ref "C14") (pin "1") (pinfunction "1_1") (pintype "passive"))
      (node (ref "C15") (pin "1") (pinfunction "1_1") (pintype "passive"))
      (node (ref "C16") (pin "1") (pinfunction "1_1") (pintype "passive"))
      (node (ref "C17") (pin "1") (pinfunction "1_1") (pintype "passive"))
      (node (ref "C18") (pin "1") (pinfunction "1_1") (pintype "passive"))
      (node (ref "C189") (pin "2") (pinfunction "2_2") (pintype "passive"))
      (node (ref "C19") (pin "1") (pinfunction "1_1") (pintype "passive"))
      (node (ref "C191") (pin "2") (pinfunction "2_2") (pintype "passive"))
      (node (ref "C192") (pin "2") (pinfunction "2_2") (pintype "passive"))
      (node (ref "C195") (pin "1") (pinfunction "1_1") (pintype "passive"))
      (node (ref "C196") (pin "2") (pinfunction "2_2") (pintype "passive"))
      (node (ref "C197") (pin "2") (pinfunction "2_2") (pintype "passive"))
      (node (ref "C198") (pin "1") (pinfunction "1_1") (pintype "passive"))
      (node (ref "C2") (pin "1") (pinfunction "1_1") (pintype "passive"))
      (node (ref "C20") (pin "1") (pinfunction "1_1") (pintype "passive"))
      (node (ref "C200") (pin "1") (pinfunction "1_1") (pintype "passive"))
      (node (ref "C204") (pin "1") (pinfunction "1_1") (pintype "passive"))
      (node (ref "C205") (pin "1") (pinfunction "1_1") (pintype "passive"))
      (node (ref "C206") (pin "1") (pinfunction "1_1") (pintype "passive"))
      (node (ref "C207") (pin "2") (pinfunction "2_2") (pintype "passive"))
      (node (ref "C208") (pin "2") (pinfunction "2_2") (pintype "passive"))
      (node (ref "C21") (pin "1") (pinfunction "1_1") (pintype "passive"))
      (node (ref "C22") (pin "2") (pinfunction "2_2") (pintype "passive"))
      (node (ref "C23") (pin "1") (pinfunction "1_1") (pintype "passive"))
      (node (ref "C24") (pin "1") (pinfunction "1_1") (pintype "passive"))
      (node (ref "C25") (pin "1") (pinfunction "1_1") (pintype "passive"))
      (node (ref "C26") (pin "1") (pinfunction "1_1") (pintype "passive"))
      (node (ref "C27") (pin "1") (pinfunction "1_1") (pintype "passive"))
      (node (ref "C28") (pin "1") (pinfunction "1_1") (pintype "passive"))
      (node (ref "C29") (pin "1") (pinfunction "1_1") (pintype "passive"))
      (node (ref "C3") (pin "1") (pinfunction "1_1") (pintype "passive"))
      (node (ref "C30") (pin "1") (pinfunction "1_1") (pintype "passive"))
      (node (ref "C31") (pin "1") (pinfunction "1_1") (pintype "passive"))
      (node (ref "C32") (pin "1") (pinfunction "1_1") (pintype "passive"))
      (node (ref "C33") (pin "2") (pinfunction "2_2") (pintype "passive"))
      (node (ref "C35") (pin "1") (pinfunction "1_1") (pintype "passive"))
      (node (ref "C36") (pin "2") (pinfunction "2_2") (pintype "passive"))
      (node (ref "C37") (pin "2") (pinfunction "2_2") (pintype "passive"))
      (node (ref "C38") (pin "1") (pinfunction "1_1") (pintype "passive"))
      (node (ref "C39") (pin "2") (pinfunction "2_2") (pintype "passive"))
      (node (ref "C4") (pin "1") (pinfunction "1_1") (pintype "passive"))
      (node (ref "C40") (pin "2") (pinfunction "2_2") (pintype "passive"))
      (node (ref "C41") (pin "1") (pinfunction "1_1") (pintype "passive"))
      (node (ref "C42") (pin "1") (pinfunction "1_1") (pintype "passive"))
      (node (ref "C5") (pin "2") (pinfunction "2_2") (pintype "passive"))
      (node (ref "C55") (pin "1") (pinfunction "1_1") (pintype "passive"))
      (node (ref "C6") (pin "2") (pinfunction "2_2") (pintype "passive"))
      (node (ref "C7") (pin "2") (pinfunction "2_2") (pintype "passive"))
      (node (ref "C8") (pin "1") (pinfunction "1_1") (pintype "passive"))
      (node (ref "C9") (pin "1") (pinfunction "1_1") (pintype "passive"))
      (node (ref "J1") (pin "2") (pinfunction "GND_2") (pintype "passive"))
      (node (ref "J1") (pin "4") (pinfunction "GND_4") (pintype "passive"))
      (node (ref "JP1") (pin "4") (pinfunction "4_4") (pintype "passive"))
      (node (ref "JP12") (pin "4") (pinfunction "4_4") (pintype "passive"))
      (node (ref "JP2") (pin "6") (pinfunction "6_6") (pintype "passive"))
      (node (ref "JP3") (pin "4") (pinfunction "4_4") (pintype "passive"))
      (node (ref "JP4") (pin "4") (pinfunction "4_4") (pintype "passive"))
      (node (ref "JP5") (pin "4") (pinfunction "4_4") (pintype "passive"))
      (node (ref "JP6") (pin "4") (pinfunction "4_4") (pintype "passive"))
      (node (ref "P1") (pin "12") (pinfunction "12_12") (pintype "passive"))
      (node (ref "P1") (pin "15") (pinfunction "15_15") (pintype "passive"))
      (node (ref "P1") (pin "18") (pinfunction "18_18") (pintype "passive"))
      (node (ref "P1") (pin "20") (pinfunction "20_20") (pintype "passive"))
      (node (ref "P1") (pin "3") (pinfunction "3_3") (pintype "passive"))
      (node (ref "P1") (pin "4") (pinfunction "4_4") (pintype "passive"))
      (node (ref "P1") (pin "6") (pinfunction "6_6") (pintype "passive"))
      (node (ref "P1") (pin "9") (pinfunction "9_9") (pintype "passive"))
      (node (ref "R11") (pin "1") (pinfunction "1_1") (pintype "passive"))
      (node (ref "R40") (pin "2") (pinfunction "2_2") (pintype "passive"))
      (node (ref "R7") (pin "1") (pinfunction "1_1") (pintype "passive"))
      (node (ref "U1") (pin "41") (pinfunction "TVSS_41") (pintype "passive"))
      (node (ref "U1") (pin "89") (pinfunction "ePAD--VSS_89") (pintype "passive"))
      (node (ref "U2") (pin "4") (pinfunction "GND_4") (pintype "passive"))
      (node (ref "U2") (pin "9") (pinfunction "EPAD_9") (pintype "passive"))
      (node (ref "U22") (pin "15") (pinfunction "GND_15") (pintype "power_in"))
      (node (ref "U3") (pin "2") (pinfunction "VSS_2") (pintype "power_in"))
      (node (ref "U3") (pin "7") (pinfunction "EP_7") (pintype "power_in"))
      (node (ref "U5") (pin "3") (pinfunction "Reserved_3") (pintype "passive"))
      (node (ref "U5") (pin "8") (pinfunction "GND_8") (pintype "power_in"))
      (node (ref "U5") (pin "9") (pinfunction "GND_9") (pintype "power_in"))
      (node (ref "U8") (pin "5") (pinfunction "GND_5") (pintype "power_in"))
    )
    (net (code "46") (name "ESP32_UART2_RX") (class "Default")
      (node (ref "U1") (pin "13") (pinfunction "JTAG_HPMCU_TMS_M1--JTAG_CPU_TMS_M0--UART5_TX_M0--SDMMC_D3--GPIO3_A6_u_13") (pintype "passive"))
    )
    (net (code "47") (name "ESP32_UART2_TX") (class "Default")
      (node (ref "U1") (pin "14") (pinfunction "JTAG_HPMCU_TCK_M1--JTAG_CPU_TCK_M0--UART5_RX_M0--SDMMC_D2--GPIO3_A7_u_14") (pintype "passive"))
    )
    (net (code "48") (name "GPIO_1V8") (class "Default")
      (node (ref "C197") (pin "1") (pinfunction "1_1") (pintype "passive"))
      (node (ref "C22") (pin "1") (pinfunction "1_1") (pintype "passive"))
      (node (ref "FB2") (pin "2") (pinfunction "2_2") (pintype "passive"))
      (node (ref "R10") (pin "2") (pinfunction "2_2") (pintype "passive"))
      (node (ref "R13") (pin "1") (pinfunction "1_1") (pintype "passive"))
      (node (ref "R18") (pin "2") (pinfunction "2_2") (pintype "passive"))
      (node (ref "R19") (pin "2") (pinfunction "2_2") (pintype "passive"))
      (node (ref "R2") (pin "2") (pinfunction "2_2") (pintype "passive"))
      (node (ref "R20") (pin "2") (pinfunction "2_2") (pintype "passive"))
      (node (ref "R23") (pin "2") (pinfunction "2_2") (pintype "passive"))
      (node (ref "R3") (pin "2") (pinfunction "2_2") (pintype "passive"))
      (node (ref "U1") (pin "38") (pinfunction "DDR_PLL_AVDD1V8_38") (pintype "passive"))
    )
    (net (code "49") (name "GPIO_3V3") (class "Default")
      (node (ref "C10") (pin "2") (pinfunction "2_2") (pintype "passive"))
      (node (ref "C12") (pin "2") (pinfunction "2_2") (pintype "passive"))
      (node (ref "C15") (pin "2") (pinfunction "2_2") (pintype "passive"))
      (node (ref "C192") (pin "1") (pinfunction "1_1") (pintype "passive"))
      (node (ref "C196") (pin "1") (pinfunction "1_1") (pintype "passive"))
      (node (ref "C198") (pin "2") (pinfunction "2_2") (pintype "passive"))
      (node (ref "C200") (pin "2") (pinfunction "2_2") (pintype "passive"))
      (node (ref "C206") (pin "2") (pinfunction "2_2") (pintype "passive"))
      (node (ref "C207") (pin "1") (pinfunction "1_1") (pintype "passive"))
      (node (ref "C208") (pin "1") (pinfunction "1_1") (pintype "passive"))
      (node (ref "C33") (pin "1") (pinfunction "1_1") (pintype "passive"))
      (node (ref "C35") (pin "2") (pinfunction "2_2") (pintype "passive"))
      (node (ref "C36") (pin "1") (pinfunction "1_1") (pintype "passive"))
      (node (ref "C37") (pin "1") (pinfunction "1_1") (pintype "passive"))
      (node (ref "C39") (pin "1") (pinfunction "1_1") (pintype "passive"))
      (node (ref "C40") (pin "1") (pinfunction "1_1") (pintype "passive"))
      (node (ref "C41") (pin "2") (pinfunction "2_2") (pintype "passive"))
      (node (ref "C55") (pin "2") (pinfunction "2_2") (pintype "passive"))
      (node (ref "JP1") (pin "1") (pinfunction "1_1") (pintype "passive"))
      (node (ref "JP12") (pin "1") (pinfunction "1_1") (pintype "passive"))
      (node (ref "JP2") (pin "1") (pinfunction "1_1") (pintype "passive"))
      (node (ref "JP3") (pin "1") (pinfunction "1_1") (pintype "passive"))
      (node (ref "JP4") (pin "1") (pinfunction "1_1") (pintype "passive"))
      (node (ref "JP5") (pin "1") (pinfunction "1_1") (pintype "passive"))
      (node (ref "JP6") (pin "1") (pinfunction "1_1") (pintype "passive"))
      (node (ref "P1") (pin "1") (pinfunction "1_1") (pintype "passive"))
      (node (ref "P1") (pin "2") (pinfunction "2_2") (pintype "passive"))
      (node (ref "R12") (pin "1") (pinfunction "1_1") (pintype "passive"))
      (node (ref "R125") (pin "2") (pinfunction "2_2") (pintype "passive"))
      (node (ref "R126") (pin "2") (pinfunction "2_2") (pintype "passive"))
      (node (ref "R14") (pin "2") (pinfunction "2_2") (pintype "passive"))
      (node (ref "R15") (pin "2") (pinfunction "2_2") (pintype "passive"))
      (node (ref "R16") (pin "1") (pinfunction "1_1") (pintype "passive"))
      (node (ref "R17") (pin "2") (pinfunction "2_2") (pintype "passive"))
      (node (ref "U1") (pin "20") (pinfunction "USB_AVDD3V3_20") (pintype "passive"))
      (node (ref "U1") (pin "43") (pinfunction "PMU_VCC3V3_43") (pintype "passive"))
      (node (ref "U1") (pin "51") (pinfunction "VCCIO1_VCC3V3_51") (pintype "passive"))
      (node (ref "U1") (pin "7") (pinfunction "VCCIO4_VCC3V3_7") (pintype "passive"))
      (node (ref "U1") (pin "71") (pinfunction "FEPHY_AVDD3V3_71") (pintype "passive"))
      (node (ref "U22") (pin "16") (pinfunction "VCC_16") (pintype "power_in"))
      (node (ref "U3") (pin "5") (pinfunction "VDD_5") (pintype "power_in"))
      (node (ref "U5") (pin "1") (pinfunction "Vdd_IO_1") (pintype "power_in"))
      (node (ref "U5") (pin "10") (pinfunction "VDD_10") (pintype "power_in"))
      (node (ref "U8") (pin "8") (pinfunction "VCC_8") (pintype "power_in"))
    )
    (net (code "50") (name "Net-(B1-Pad1)") (class "Default")
      (node (ref "B1") (pin "1") (pinfunction "1_1") (pintype "passive"))
      (node (ref "R4") (pin "1") (pinfunction "1_1") (pintype "passive"))
    )
    (net (code "51") (name "Net-(J1-OSC1)") (class "Default")
      (node (ref "C1") (pin "2") (pinfunction "2_2") (pintype "passive"))
      (node (ref "J1") (pin "1") (pinfunction "OSC1_1") (pintype "passive"))
      (node (ref "R1") (pin "1") (pinfunction "1_1") (pintype "passive"))
      (node (ref "U1") (pin "46") (pinfunction "OSC_SOC_XOUT_46") (pintype "passive"))
    )
    (net (code "52") (name "Net-(J1-OSC2)") (class "Default")
      (node (ref "C2") (pin "2") (pinfunction "2_2") (pintype "passive"))
      (node (ref "J1") (pin "3") (pinfunction "OSC2_3") (pintype "passive"))
      (node (ref "R1") (pin "2") (pinfunction "2_2") (pintype "passive"))
      (node (ref "U1") (pin "45") (pinfunction "OSC_SOC_XIN_45") (pintype "passive"))
    )
    (net (code "53") (name "Net-(U1A-JTAG_HPMCU_TCK_M0--JTAG_CPU_TCK_M1--UART2_TX_M1--GPIO1_B2_d)") (class "Default")
      (node (ref "R5") (pin "1") (pinfunction "1_1") (pintype "passive"))
      (node (ref "U1") (pin "49") (pinfunction "JTAG_HPMCU_TCK_M0--JTAG_CPU_TCK_M1--UART2_TX_M1--GPIO1_B2_d_49") (pintype "passive"))
    )
    (net (code "54") (name "Net-(U1A-JTAG_HPMCU_TMS_M0--JTAG_CPU_TMS_M1--UART2_RX_M1--GPIO1_B3_u)") (class "Default")
      (node (ref "R6") (pin "1") (pinfunction "1_1") (pintype "passive"))
      (node (ref "U1") (pin "50") (pinfunction "JTAG_HPMCU_TMS_M0--JTAG_CPU_TMS_M1--UART2_RX_M1--GPIO1_B3_u_50") (pintype "passive"))
    )
    (net (code "55") (name "Net-(U1A-OTP_AVDD1V8--ETH_AVDD1V8--TSADC_AVDD1V8)") (class "Default")
      (node (ref "FB1") (pin "1") (pinfunction "1_1") (pintype "passive"))
      (node (ref "U1") (pin "66") (pinfunction "OTP_AVDD1V8--ETH_AVDD1V8--TSADC_AVDD1V8_66") (pintype "passive"))
    )
    (net (code "56") (name "Net-(U1B-MIPI_AVDD1V8--VCCIO7_VCC1V8)") (class "Default")
      (node (ref "C42") (pin "2") (pinfunction "2_2") (pintype "passive"))
      (node (ref "R23") (pin "1") (pinfunction "1_1") (pintype "passive"))
      (node (ref "U1") (pin "88") (pinfunction "MIPI_AVDD1V8--VCCIO7_VCC1V8_88") (pintype "passive"))
    )
    (net (code "57") (name "Net-(U1B-VCCIO6_VCC)") (class "Default")
      (node (ref "C38") (pin "2") (pinfunction "2_2") (pintype "passive"))
      (node (ref "R17") (pin "1") (pinfunction "1_1") (pintype "passive"))
      (node (ref "R20") (pin "1") (pinfunction "1_1") (pintype "passive"))
      (node (ref "U1") (pin "59") (pinfunction "VCCIO6_VCC_59") (pintype "passive"))
    )
    (net (code "58") (name "Net-(U1C-CODEC_VCM)") (class "Default")
      (node (ref "C5") (pin "1") (pinfunction "1_1") (pintype "passive"))
      (node (ref "U1") (pin "22") (pinfunction "CODEC_VCM_22") (pintype "passive"))
    )
    (net (code "59") (name "Net-(U1C-DRAM_ZQ)") (class "Default")
      (node (ref "R7") (pin "2") (pinfunction "2_2") (pintype "passive"))
      (node (ref "U1") (pin "37") (pinfunction "DRAM_ZQ_37") (pintype "passive"))
    )
    (net (code "60") (name "Net-(U1C-FEPHY_EXTR)") (class "Default")
      (node (ref "R11") (pin "2") (pinfunction "2_2") (pintype "passive"))
      (node (ref "U1") (pin "72") (pinfunction "FEPHY_EXTR_72") (pintype "passive"))
    )
    (net (code "61") (name "Net-(U1C-SARADC_USB_AVDD1V8)") (class "Default")
      (node (ref "C11") (pin "2") (pinfunction "2_2") (pintype "passive"))
      (node (ref "R10") (pin "1") (pinfunction "1_1") (pintype "passive"))
      (node (ref "U1") (pin "17") (pinfunction "SARADC_USB_AVDD1V8_17") (pintype "passive"))
    )
    (net (code "62") (name "Net-(U5-CS)") (class "Default")
      (node (ref "R16") (pin "2") (pinfunction "2_2") (pintype "passive"))
      (node (ref "U5") (pin "6") (pinfunction "CS_6") (pintype "input"))
    )
    (net (code "63") (name "Net-(U8-~{RE})") (class "Default")
      (node (ref "R40") (pin "1") (pinfunction "1_1") (pintype "passive"))
      (node (ref "U8") (pin "2") (pinfunction "~{RE}_2") (pintype "output"))
    )
    (net (code "64") (name "Net-(U22-C1+)") (class "Default")
      (node (ref "C190") (pin "2") (pinfunction "2_2") (pintype "passive"))
      (node (ref "U22") (pin "1") (pinfunction "C1+_1") (pintype "passive"))
    )
    (net (code "65") (name "Net-(U22-C1-)") (class "Default")
      (node (ref "C190") (pin "1") (pinfunction "1_1") (pintype "passive"))
      (node (ref "U22") (pin "3") (pinfunction "C1-_3") (pintype "passive"))
    )
    (net (code "66") (name "Net-(U22-C2+)") (class "Default")
      (node (ref "C193") (pin "2") (pinfunction "2_2") (pintype "passive"))
      (node (ref "U22") (pin "4") (pinfunction "C2+_4") (pintype "passive"))
    )
    (net (code "67") (name "Net-(U22-C2-)") (class "Default")
      (node (ref "C193") (pin "1") (pinfunction "1_1") (pintype "passive"))
      (node (ref "U22") (pin "5") (pinfunction "C2-_5") (pintype "passive"))
    )
    (net (code "68") (name "Net-(U22-V+)") (class "Default")
      (node (ref "C189") (pin "1") (pinfunction "1_1") (pintype "passive"))
      (node (ref "U22") (pin "2") (pinfunction "V+_2") (pintype "passive"))
    )
    (net (code "69") (name "Net-(U22-V-)") (class "Default")
      (node (ref "C191") (pin "1") (pinfunction "1_1") (pintype "passive"))
      (node (ref "U22") (pin "6") (pinfunction "V-_6") (pintype "passive"))
    )
    (net (code "70") (name "RV1103_D_N") (class "Default")
      (node (ref "U1") (pin "18") (pinfunction "USB_DM_18") (pintype "passive"))
    )
    (net (code "71") (name "RV1103_D_P") (class "Default")
      (node (ref "U1") (pin "19") (pinfunction "USB_DP_19") (pintype "passive"))
    )
    (net (code "72") (name "RV1103_ETH_RX_N") (class "Default")
      (node (ref "U1") (pin "67") (pinfunction "FEPHY_RXN_67") (pintype "passive"))
    )
    (net (code "73") (name "RV1103_ETH_RX_P") (class "Default")
      (node (ref "U1") (pin "68") (pinfunction "FEPHY_RXP_68") (pintype "passive"))
    )
    (net (code "74") (name "RV1103_ETH_TX_N") (class "Default")
      (node (ref "U1") (pin "69") (pinfunction "FEPHY_TXN_69") (pintype "passive"))
    )
    (net (code "75") (name "RV1103_ETH_TX_P") (class "Default")
      (node (ref "U1") (pin "70") (pinfunction "FEPHY_TXP_70") (pintype "passive"))
    )
    (net (code "76") (name "VCCIO_FLASH") (class "Default")
      (node (ref "C13") (pin "2") (pinfunction "2_2") (pintype "passive"))
      (node (ref "C14") (pin "2") (pinfunction "2_2") (pintype "passive"))
      (node (ref "C16") (pin "2") (pinfunction "2_2") (pintype "passive"))
      (node (ref "R12") (pin "2") (pinfunction "2_2") (pintype "passive"))
      (node (ref "R13") (pin "2") (pinfunction "2_2") (pintype "passive"))
      (node (ref "R8") (pin "2") (pinfunction "2_2") (pintype "passive"))
      (node (ref "R9") (pin "2") (pinfunction "2_2") (pintype "passive"))
      (node (ref "U1") (pin "27") (pinfunction "VCCIO3_VCC_27") (pintype "passive"))
      (node (ref "U2") (pin "8") (pinfunction "VCC_8") (pintype "passive"))
    )
    (net (code "77") (name "unconnected-(P1-SH-Pad0)") (class "Default")
      (node (ref "P1") (pin "0") (pinfunction "SH_0") (pintype "passive+no_connect"))
    )
    (net (code "78") (name "unconnected-(P1-SH-Pad0)_1") (class "Default")
      (node (ref "P1") (pin "0") (pinfunction "SH_0") (pintype "passive+no_connect"))
    )
    (net (code "79") (name "unconnected-(U1A-PWM1_M0--PWR_CTRL_M0--GPIO0_A4_d-Pad42)") (class "Default")
      (node (ref "U1") (pin "42") (pinfunction "PWM1_M0--PWR_CTRL_M0--GPIO0_A4_d_42") (pintype "passive+no_connect"))
    )
    (net (code "80") (name "unconnected-(U1B-LVDS_RX_CLK1N--MIPI_CSI_RX_CLK1N--GPI3_B2_d-Pad78)") (class "Default")
      (node (ref "U1") (pin "78") (pinfunction "LVDS_RX_CLK1N--MIPI_CSI_RX_CLK1N--GPI3_B2_d_78") (pintype "passive+no_connect"))
    )
    (net (code "81") (name "unconnected-(U1B-LVDS_RX_CLK1P--MIPI_CSI_RX_CLK1P--GPI3_B3_d-Pad79)") (class "Default")
      (node (ref "U1") (pin "79") (pinfunction "LVDS_RX_CLK1P--MIPI_CSI_RX_CLK1P--GPI3_B3_d_79") (pintype "passive+no_connect"))
    )
    (net (code "82") (name "unconnected-(U1B-LVDS_RX_D2N--MIPI_CSI_RX_D2N--GPI3_B4_d-Pad80)") (class "Default")
      (node (ref "U1") (pin "80") (pinfunction "LVDS_RX_D2N--MIPI_CSI_RX_D2N--GPI3_B4_d_80") (pintype "passive+no_connect"))
    )
    (net (code "83") (name "unconnected-(U1B-LVDS_RX_D2P--MIPI_CSI_RX_D2P--GPI3_B5_d-Pad81)") (class "Default")
      (node (ref "U1") (pin "81") (pinfunction "LVDS_RX_D2P--MIPI_CSI_RX_D2P--GPI3_B5_d_81") (pintype "passive+no_connect"))
    )
    (net (code "84") (name "unconnected-(U1B-LVDS_RX_D3N--MIPI_CSI_RX_D3N--GPI3_B0_d-Pad76)") (class "Default")
      (node (ref "U1") (pin "76") (pinfunction "LVDS_RX_D3N--MIPI_CSI_RX_D3N--GPI3_B0_d_76") (pintype "passive+no_connect"))
    )
    (net (code "85") (name "unconnected-(U1B-LVDS_RX_D3P--MIPI_CSI_RX_D3P--GPI3_B1_d-Pad77)") (class "Default")
      (node (ref "U1") (pin "77") (pinfunction "LVDS_RX_D3P--MIPI_CSI_RX_D3P--GPI3_B1_d_77") (pintype "passive+no_connect"))
    )
    (net (code "86") (name "unconnected-(U1B-PWM7_IR_M2--MIPI-CLK1_OUT--GPIO3_C6_d-Pad3)") (class "Default")
      (node (ref "U1") (pin "3") (pinfunction "PWM7_IR_M2--MIPI-CLK1_OUT--GPIO3_C6_d_3") (pintype "passive+no_connect"))
    )
    (net (code "87") (name "unconnected-(U1B-PWM8_M0--UART2_RX_M0--SDMMC_D0--GPIO3_A3_u-Pad10)") (class "Default")
      (node (ref "U1") (pin "10") (pinfunction "PWM8_M0--UART2_RX_M0--SDMMC_D0--GPIO3_A3_u_10") (pintype "passive+no_connect"))
    )
    (net (code "88") (name "unconnected-(U1B-PWM9_M0--UART2_TX_M0--SDMMC_D1--GPIO3_A2_u-Pad9)") (class "Default")
      (node (ref "U1") (pin "9") (pinfunction "PWM9_M0--UART2_TX_M0--SDMMC_D1--GPIO3_A2_u_9") (pintype "passive+no_connect"))
    )
    (net (code "89") (name "unconnected-(U1B-SDMMC_DET--GPIO3_A1_u-Pad8)") (class "Default")
      (node (ref "U1") (pin "8") (pinfunction "SDMMC_DET--GPIO3_A1_u_8") (pintype "passive+no_connect"))
    )
    (net (code "90") (name "unconnected-(U1B-UART4_CTS_M1--PWM11_IR_M1--GPIO1_C7_d-Pad53)") (class "Default")
      (node (ref "U1") (pin "53") (pinfunction "UART4_CTS_M1--PWM11_IR_M1--GPIO1_C7_d_53") (pintype "passive+no_connect"))
    )
    (net (code "91") (name "unconnected-(U1B-UART4_RTS_M1--PWM10_M1--GPIO1_C6_d-Pad52)") (class "Default")
      (node (ref "U1") (pin "52") (pinfunction "UART4_RTS_M1--PWM10_M1--GPIO1_C6_d_52") (pintype "passive+no_connect"))
    )
    (net (code "92") (name "unconnected-(U1C-CODEC_LINEOUT-Pad21)") (class "Default")
      (node (ref "U1") (pin "21") (pinfunction "CODEC_LINEOUT_21") (pintype "passive+no_connect"))
    )
    (net (code "93") (name "unconnected-(U1C-CODEC_MIC0P_MICP-Pad24)") (class "Default")
      (node (ref "U1") (pin "24") (pinfunction "CODEC_MIC0P_MICP_24") (pintype "passive+no_connect"))
    )
    (net (code "94") (name "unconnected-(U1C-CODEC_MIC1P_MICN-Pad26)") (class "Default")
      (node (ref "U1") (pin "26") (pinfunction "CODEC_MIC1P_MICN_26") (pintype "passive+no_connect"))
    )
    (net (code "95") (name "unconnected-(U1C-CODEC_MICBIAS-Pad25)") (class "Default")
      (node (ref "U1") (pin "25") (pinfunction "CODEC_MICBIAS_25") (pintype "passive+no_connect"))
    )
    (net (code "96") (name "unconnected-(U3-NC-Pad3)") (class "Default")
      (node (ref "U3") (pin "3") (pinfunction "NC_3") (pintype "passive+no_connect"))
    )
    (net (code "97") (name "unconnected-(U3-NC-Pad4)") (class "Default")
      (node (ref "U3") (pin "4") (pinfunction "NC_4") (pintype "passive+no_connect"))
    )
    (net (code "98") (name "unconnected-(U5-INT_DRDY-Pad7)") (class "Default")
      (node (ref "U5") (pin "7") (pinfunction "INT_DRDY_7") (pintype "output+no_connect"))
    )
    (net (code "99") (name "unconnected-(U5-SDO{slash}SA0-Pad5)") (class "Default")
      (node (ref "U5") (pin "5") (pinfunction "SDO/SA0_5") (pintype "output"))
    )
    (net (code "100") (name "unconnected-(U22-R2IN-Pad8)") (class "Default")
      (node (ref "U22") (pin "8") (pinfunction "R2IN_8") (pintype "input+no_connect"))
    )
    (net (code "101") (name "unconnected-(U22-R2OUT-Pad9)") (class "Default")
      (node (ref "U22") (pin "9") (pinfunction "R2OUT_9") (pintype "output+no_connect"))
    )
    (net (code "102") (name "unconnected-(U22-T2IN-Pad10)") (class "Default")
      (node (ref "U22") (pin "10") (pinfunction "T2IN_10") (pintype "input+no_connect"))
    )
    (net (code "103") (name "unconnected-(U22-T2OUT-Pad7)") (class "Default")
      (node (ref "U22") (pin "7") (pinfunction "T2OUT_7") (pintype "output+no_connect"))
    )
  )
)
